# Breakout_14Pin.net
KiCad netlist of a schematic drawn in EAGLE
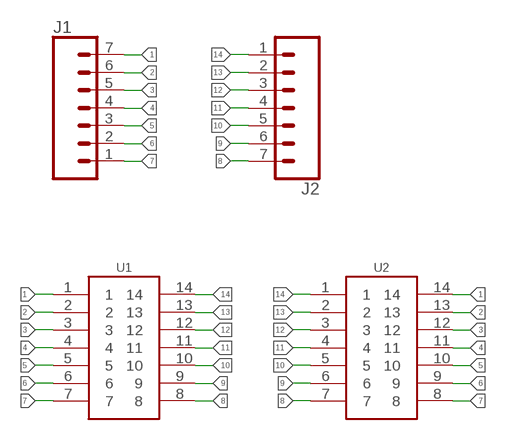
[diagram p0: schematic, sheet 1]

(export (version "E")
  (design (tool "Eeschema 10.0.6"))
  (components
    (comp (ref "J1")
      (value "CONN_07")
      (footprint "eagle-import:1X07")
      (libsource (lib "eagle-import") (part "CONN_07"))
    )
    (comp (ref "J2")
      (value "CONN_07")
      (footprint "eagle-import:1X07")
      (libsource (lib "eagle-import") (part "CONN_07"))
    )
    (comp (ref "U1")
      (value "GEN_14SOIC")
      (footprint "eagle-import:SO14")
      (libsource (lib "eagle-import") (part "GEN_14SOIC"))
    )
    (comp (ref "U2")
      (value "GEN_14TSSOP")
      (footprint "eagle-import:TSSOP14")
      (libsource (lib "eagle-import") (part "GEN_14TSSOP"))
    )
  )
  (nets
    (net (code "1") (name "1") (class "Default")
      (node (ref "J1") (pin "7") (pinfunction "7_7") (pintype "passive"))
      (node (ref "U1") (pin "1") (pinfunction "1_1") (pintype "bidirectional"))
      (node (ref "U2") (pin "14") (pinfunction "14_14") (pintype "bidirectional"))
    )
    (net (code "2") (name "2") (class "Default")
      (node (ref "J1") (pin "6") (pinfunction "6_6") (pintype "passive"))
      (node (ref "U1") (pin "2") (pinfunction "2_2") (pintype "bidirectional"))
      (node (ref "U2") (pin "13") (pinfunction "13_13") (pintype "bidirectional"))
    )
    (net (code "3") (name "3") (class "Default")
      (node (ref "J1") (pin "5") (pinfunction "5_5") (pintype "passive"))
      (node (ref "U1") (pin "3") (pinfunction "3_3") (pintype "bidirectional"))
      (node (ref "U2") (pin "12") (pinfunction "12_12") (pintype "bidirectional"))
    )
    (net (code "4") (name "4") (class "Default")
      (node (ref "J1") (pin "4") (pinfunction "4_4") (pintype "passive"))
      (node (ref "U1") (pin "4") (pinfunction "4_4") (pintype "bidirectional"))
      (node (ref "U2") (pin "11") (pinfunction "11_11") (pintype "bidirectional"))
    )
    (net (code "5") (name "5") (class "Default")
      (node (ref "J1") (pin "3") (pinfunction "3_3") (pintype "passive"))
      (node (ref "U1") (pin "5") (pinfunction "5_5") (pintype "bidirectional"))
      (node (ref "U2") (pin "10") (pinfunction "10_10") (pintype "bidirectional"))
    )
    (net (code "6") (name "6") (class "Default")
      (node (ref "J1") (pin "2") (pinfunction "2_2") (pintype "passive"))
      (node (ref "U1") (pin "6") (pinfunction "6_6") (pintype "bidirectional"))
      (node (ref "U2") (pin "9") (pinfunction "9_9") (pintype "bidirectional"))
    )
    (net (code "7") (name "7") (class "Default")
      (node (ref "J1") (pin "1") (pinfunction "1_1") (pintype "passive"))
      (node (ref "U1") (pin "7") (pinfunction "7_7") (pintype "bidirectional"))
      (node (ref "U2") (pin "8") (pinfunction "8_8") (pintype "bidirectional"))
    )
    (net (code "8") (name "8") (class "Default")
      (node (ref "J2") (pin "7") (pinfunction "7_7") (pintype "passive"))
      (node (ref "U1") (pin "8") (pinfunction "8_8") (pintype "bidirectional"))
      (node (ref "U2") (pin "7") (pinfunction "7_7") (pintype "bidirectional"))
    )
    (net (code "9") (name "9") (class "Default")
      (node (ref "J2") (pin "6") (pinfunction "6_6") (pintype "passive"))
      (node (ref "U1") (pin "9") (pinfunction "9_9") (pintype "bidirectional"))
      (node (ref "U2") (pin "6") (pinfunction "6_6") (pintype "bidirectional"))
    )
    (net (code "10") (name "10") (class "Default")
      (node (ref "J2") (pin "5") (pinfunction "5_5") (pintype "passive"))
      (node (ref "U1") (pin "10") (pinfunction "10_10") (pintype "bidirectional"))
      (node (ref "U2") (pin "5") (pinfunction "5_5") (pintype "bidirectional"))
    )
    (net (code "11") (name "11") (class "Default")
      (node (ref "J2") (pin "4") (pinfunction "4_4") (pintype "passive"))
      (node (ref "U1") (pin "11") (pinfunction "11_11") (pintype "bidirectional"))
      (node (ref "U2") (pin "4") (pinfunction "4_4") (pintype "bidirectional"))
    )
    (net (code "12") (name "12") (class "Default")
      (node (ref "J2") (pin "3") (pinfunction "3_3") (pintype "passive"))
      (node (ref "U1") (pin "12") (pinfunction "12_12") (pintype "bidirectional"))
      (node (ref "U2") (pin "3") (pinfunction "3_3") (pintype "bidirectional"))
    )
    (net (code "13") (name "13") (class "Default")
      (node (ref "J2") (pin "2") (pinfunction "2_2") (pintype "passive"))
      (node (ref "U1") (pin "13") (pinfunction "13_13") (pintype "bidirectional"))
      (node (ref "U2") (pin "2") (pinfunction "2_2") (pintype "bidirectional"))
    )
    (net (code "14") (name "14") (class "Default")
      (node (ref "J2") (pin "1") (pinfunction "1_1") (pintype "passive"))
      (node (ref "U1") (pin "14") (pinfunction "14_14") (pintype "bidirectional"))
      (node (ref "U2") (pin "1") (pinfunction "1_1") (pintype "bidirectional"))
    )
  )
)
